# Bypass_FPGA_1V2.net
KiCad netlist of a schematic drawn in Altium Designer
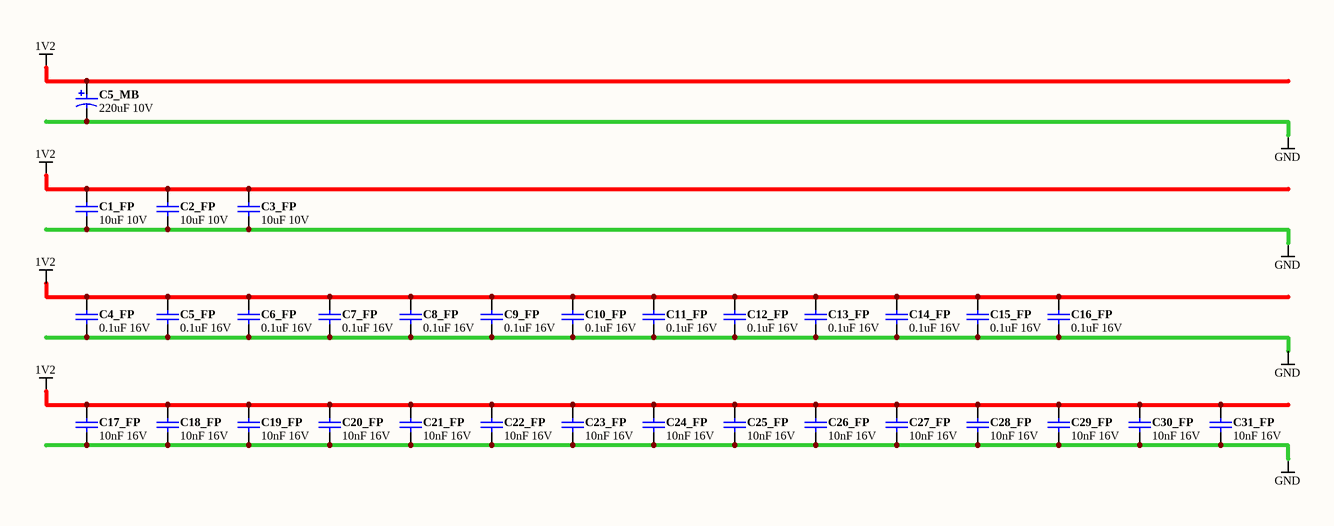
[diagram p0: Bypass_FPGA_1V2.SCHDOC]

(export (version "E")
  (design (tool "Eeschema 10.0.6"))
  (components
    (comp (ref "C1_FP")
      (value "10uF 10V")
      (footprint "CAPC2012-STAR")
      (description "Capacitor, Ceramic, 10uF 10% 10V 0805 (2012) X5R")
      (fields (field (name "TOLERANCE") "10 %"))
      (libsource (lib "AltiumDesignLibrary") (part "CAP-NP"))
    )
    (comp (ref "C2_FP")
      (value "10uF 10V")
      (footprint "CAPC2012-STAR")
      (description "Capacitor, Ceramic, 10uF 10% 10V 0805 (2012) X5R")
      (fields (field (name "TOLERANCE") "10 %"))
      (libsource (lib "AltiumDesignLibrary") (part "CAP-NP"))
    )
    (comp (ref "C3_FP")
      (value "10uF 10V")
      (footprint "CAPC2012-STAR")
      (description "Capacitor, Ceramic, 10uF 10% 10V 0805 (2012) X5R")
      (fields (field (name "TOLERANCE") "10 %"))
      (libsource (lib "AltiumDesignLibrary") (part "CAP-NP"))
    )
    (comp (ref "C4_FP")
      (value "0.1uF 16V")
      (footprint "CAPC1005-STAR")
      (description "Capacitor, Ceramic, 0.1uF 10% 16V 0402 (1005) X7R")
      (fields (field (name "TOLERANCE") "10 %"))
      (libsource (lib "AltiumDesignLibrary") (part "CAP-NP"))
    )
    (comp (ref "C5_FP")
      (value "0.1uF 16V")
      (footprint "CAPC1005-STAR")
      (description "Capacitor, Ceramic, 0.1uF 10% 16V 0402 (1005) X7R")
      (fields (field (name "TOLERANCE") "10 %"))
      (libsource (lib "AltiumDesignLibrary") (part "CAP-NP"))
    )
    (comp (ref "C5_MB")
      (value "220uF 10V")
      (footprint "CAPC7343-STAR")
      (description "Capacitor, Tantalum, 220uF 10% 10V MCCT-D (7343-31)")
      (fields (field (name "TOLERANCE") "10 %"))
      (libsource (lib "AltiumDesignLibrary") (part "CAP-P"))
    )
    (comp (ref "C6_FP")
      (value "0.1uF 16V")
      (footprint "CAPC1005-STAR")
      (description "Capacitor, Ceramic, 0.1uF 10% 16V 0402 (1005) X7R")
      (fields (field (name "TOLERANCE") "10 %"))
      (libsource (lib "AltiumDesignLibrary") (part "CAP-NP"))
    )
    (comp (ref "C7_FP")
      (value "0.1uF 16V")
      (footprint "CAPC1005-STAR")
      (description "Capacitor, Ceramic, 0.1uF 10% 16V 0402 (1005) X7R")
      (fields (field (name "TOLERANCE") "10 %"))
      (libsource (lib "AltiumDesignLibrary") (part "CAP-NP"))
    )
    (comp (ref "C8_FP")
      (value "0.1uF 16V")
      (footprint "CAPC1005-STAR")
      (description "Capacitor, Ceramic, 0.1uF 10% 16V 0402 (1005) X7R")
      (fields (field (name "TOLERANCE") "10 %"))
      (libsource (lib "AltiumDesignLibrary") (part "CAP-NP"))
    )
    (comp (ref "C9_FP")
      (value "0.1uF 16V")
      (footprint "CAPC1005-STAR")
      (description "Capacitor, Ceramic, 0.1uF 10% 16V 0402 (1005) X7R")
      (fields (field (name "TOLERANCE") "10 %"))
      (libsource (lib "AltiumDesignLibrary") (part "CAP-NP"))
    )
    (comp (ref "C10_FP")
      (value "0.1uF 16V")
      (footprint "CAPC1005-STAR")
      (description "Capacitor, Ceramic, 0.1uF 10% 16V 0402 (1005) X7R")
      (fields (field (name "TOLERANCE") "10 %"))
      (libsource (lib "AltiumDesignLibrary") (part "CAP-NP"))
    )
    (comp (ref "C11_FP")
      (value "0.1uF 16V")
      (footprint "CAPC1005-STAR")
      (description "Capacitor, Ceramic, 0.1uF 10% 16V 0402 (1005) X7R")
      (fields (field (name "TOLERANCE") "10 %"))
      (libsource (lib "AltiumDesignLibrary") (part "CAP-NP"))
    )
    (comp (ref "C12_FP")
      (value "0.1uF 16V")
      (footprint "CAPC1005-STAR")
      (description "Capacitor, Ceramic, 0.1uF 10% 16V 0402 (1005) X7R")
      (fields (field (name "TOLERANCE") "10 %"))
      (libsource (lib "AltiumDesignLibrary") (part "CAP-NP"))
    )
    (comp (ref "C13_FP")
      (value "0.1uF 16V")
      (footprint "CAPC1005-STAR")
      (description "Capacitor, Ceramic, 0.1uF 10% 16V 0402 (1005) X7R")
      (fields (field (name "TOLERANCE") "10 %"))
      (libsource (lib "AltiumDesignLibrary") (part "CAP-NP"))
    )
    (comp (ref "C14_FP")
      (value "0.1uF 16V")
      (footprint "CAPC1005-STAR")
      (description "Capacitor, Ceramic, 0.1uF 10% 16V 0402 (1005) X7R")
      (fields (field (name "TOLERANCE") "10 %"))
      (libsource (lib "AltiumDesignLibrary") (part "CAP-NP"))
    )
    (comp (ref "C15_FP")
      (value "0.1uF 16V")
      (footprint "CAPC1005-STAR")
      (description "Capacitor, Ceramic, 0.1uF 10% 16V 0402 (1005) X7R")
      (fields (field (name "TOLERANCE") "10 %"))
      (libsource (lib "AltiumDesignLibrary") (part "CAP-NP"))
    )
    (comp (ref "C16_FP")
      (value "0.1uF 16V")
      (footprint "CAPC1005-STAR")
      (description "Capacitor, Ceramic, 0.1uF 10% 16V 0402 (1005) X7R")
      (fields (field (name "TOLERANCE") "10 %"))
      (libsource (lib "AltiumDesignLibrary") (part "CAP-NP"))
    )
    (comp (ref "C17_FP")
      (value "10nF 16V")
      (footprint "CAPC1005-STAR")
      (description "Capacitor, Ceramic, 10nF 10% 16V 0402 (1005) X7R")
      (fields (field (name "TOLERANCE") "10 %"))
      (libsource (lib "AltiumDesignLibrary") (part "CAP-NP"))
    )
    (comp (ref "C18_FP")
      (value "10nF 16V")
      (footprint "CAPC1005-STAR")
      (description "Capacitor, Ceramic, 10nF 10% 16V 0402 (1005) X7R")
      (fields (field (name "TOLERANCE") "10 %"))
      (libsource (lib "AltiumDesignLibrary") (part "CAP-NP"))
    )
    (comp (ref "C19_FP")
      (value "10nF 16V")
      (footprint "CAPC1005-STAR")
      (description "Capacitor, Ceramic, 10nF 10% 16V 0402 (1005) X7R")
      (fields (field (name "TOLERANCE") "10 %"))
      (libsource (lib "AltiumDesignLibrary") (part "CAP-NP"))
    )
    (comp (ref "C20_FP")
      (value "10nF 16V")
      (footprint "CAPC1005-STAR")
      (description "Capacitor, Ceramic, 10nF 10% 16V 0402 (1005) X7R")
      (fields (field (name "TOLERANCE") "10 %"))
      (libsource (lib "AltiumDesignLibrary") (part "CAP-NP"))
    )
    (comp (ref "C21_FP")
      (value "10nF 16V")
      (footprint "CAPC1005-STAR")
      (description "Capacitor, Ceramic, 10nF 10% 16V 0402 (1005) X7R")
      (fields (field (name "TOLERANCE") "10 %"))
      (libsource (lib "AltiumDesignLibrary") (part "CAP-NP"))
    )
    (comp (ref "C22_FP")
      (value "10nF 16V")
      (footprint "CAPC1005-STAR")
      (description "Capacitor, Ceramic, 10nF 10% 16V 0402 (1005) X7R")
      (fields (field (name "TOLERANCE") "10 %"))
      (libsource (lib "AltiumDesignLibrary") (part "CAP-NP"))
    )
    (comp (ref "C23_FP")
      (value "10nF 16V")
      (footprint "CAPC1005-STAR")
      (description "Capacitor, Ceramic, 10nF 10% 16V 0402 (1005) X7R")
      (fields (field (name "TOLERANCE") "10 %"))
      (libsource (lib "AltiumDesignLibrary") (part "CAP-NP"))
    )
    (comp (ref "C24_FP")
      (value "10nF 16V")
      (footprint "CAPC1005-STAR")
      (description "Capacitor, Ceramic, 10nF 10% 16V 0402 (1005) X7R")
      (fields (field (name "TOLERANCE") "10 %"))
      (libsource (lib "AltiumDesignLibrary") (part "CAP-NP"))
    )
    (comp (ref "C25_FP")
      (value "10nF 16V")
      (footprint "CAPC1005-STAR")
      (description "Capacitor, Ceramic, 10nF 10% 16V 0402 (1005) X7R")
      (fields (field (name "TOLERANCE") "10 %"))
      (libsource (lib "AltiumDesignLibrary") (part "CAP-NP"))
    )
    (comp (ref "C26_FP")
      (value "10nF 16V")
      (footprint "CAPC1005-STAR")
      (description "Capacitor, Ceramic, 10nF 10% 16V 0402 (1005) X7R")
      (fields (field (name "TOLERANCE") "10 %"))
      (libsource (lib "AltiumDesignLibrary") (part "CAP-NP"))
    )
    (comp (ref "C27_FP")
      (value "10nF 16V")
      (footprint "CAPC1005-STAR")
      (description "Capacitor, Ceramic, 10nF 10% 16V 0402 (1005) X7R")
      (fields (field (name "TOLERANCE") "10 %"))
      (libsource (lib "AltiumDesignLibrary") (part "CAP-NP"))
    )
    (comp (ref "C28_FP")
      (value "10nF 16V")
      (footprint "CAPC1005-STAR")
      (description "Capacitor, Ceramic, 10nF 10% 16V 0402 (1005) X7R")
      (fields (field (name "TOLERANCE") "10 %"))
      (libsource (lib "AltiumDesignLibrary") (part "CAP-NP"))
    )
    (comp (ref "C29_FP")
      (value "10nF 16V")
      (footprint "CAPC1005-STAR")
      (description "Capacitor, Ceramic, 10nF 10% 16V 0402 (1005) X7R")
      (fields (field (name "TOLERANCE") "10 %"))
      (libsource (lib "AltiumDesignLibrary") (part "CAP-NP"))
    )
    (comp (ref "C30_FP")
      (value "10nF 16V")
      (footprint "CAPC1005-STAR")
      (description "Capacitor, Ceramic, 10nF 10% 16V 0402 (1005) X7R")
      (fields (field (name "TOLERANCE") "10 %"))
      (libsource (lib "AltiumDesignLibrary") (part "CAP-NP"))
    )
    (comp (ref "C31_FP")
      (value "10nF 16V")
      (footprint "CAPC1005-STAR")
      (description "Capacitor, Ceramic, 10nF 10% 16V 0402 (1005) X7R")
      (fields (field (name "TOLERANCE") "10 %"))
      (libsource (lib "AltiumDesignLibrary") (part "CAP-NP"))
    )
  )
  (nets
    (net (code "1") (name "1V2") (class "Default")
      (node (ref "C10_FP") (pin "1") (pinfunction "1_1") (pintype "passive"))
      (node (ref "C11_FP") (pin "1") (pinfunction "1_1") (pintype "passive"))
      (node (ref "C12_FP") (pin "1") (pinfunction "1_1") (pintype "passive"))
      (node (ref "C13_FP") (pin "1") (pinfunction "1_1") (pintype "passive"))
      (node (ref "C14_FP") (pin "1") (pinfunction "1_1") (pintype "passive"))
      (node (ref "C15_FP") (pin "1") (pinfunction "1_1") (pintype "passive"))
      (node (ref "C16_FP") (pin "1") (pinfunction "1_1") (pintype "passive"))
      (node (ref "C17_FP") (pin "1") (pinfunction "1_1") (pintype "passive"))
      (node (ref "C18_FP") (pin "1") (pinfunction "1_1") (pintype "passive"))
      (node (ref "C19_FP") (pin "1") (pinfunction "1_1") (pintype "passive"))
      (node (ref "C1_FP") (pin "1") (pinfunction "1_1") (pintype "passive"))
      (node (ref "C20_FP") (pin "1") (pinfunction "1_1") (pintype "passive"))
      (node (ref "C21_FP") (pin "1") (pinfunction "1_1") (pintype "passive"))
      (node (ref "C22_FP") (pin "1") (pinfunction "1_1") (pintype "passive"))
      (node (ref "C23_FP") (pin "1") (pinfunction "1_1") (pintype "passive"))
      (node (ref "C24_FP") (pin "1") (pinfunction "1_1") (pintype "passive"))
      (node (ref "C25_FP") (pin "1") (pinfunction "1_1") (pintype "passive"))
      (node (ref "C26_FP") (pin "1") (pinfunction "1_1") (pintype "passive"))
      (node (ref "C27_FP") (pin "1") (pinfunction "1_1") (pintype "passive"))
      (node (ref "C28_FP") (pin "1") (pinfunction "1_1") (pintype "passive"))
      (node (ref "C29_FP") (pin "1") (pinfunction "1_1") (pintype "passive"))
      (node (ref "C2_FP") (pin "1") (pinfunction "1_1") (pintype "passive"))
      (node (ref "C30_FP") (pin "1") (pinfunction "1_1") (pintype "passive"))
      (node (ref "C31_FP") (pin "1") (pinfunction "1_1") (pintype "passive"))
      (node (ref "C3_FP") (pin "1") (pinfunction "1_1") (pintype "passive"))
      (node (ref "C4_FP") (pin "1") (pinfunction "1_1") (pintype "passive"))
      (node (ref "C5_FP") (pin "1") (pinfunction "1_1") (pintype "passive"))
      (node (ref "C5_MB") (pin "1") (pinfunction "1_1") (pintype "passive"))
      (node (ref "C6_FP") (pin "1") (pinfunction "1_1") (pintype "passive"))
      (node (ref "C7_FP") (pin "1") (pinfunction "1_1") (pintype "passive"))
      (node (ref "C8_FP") (pin "1") (pinfunction "1_1") (pintype "passive"))
      (node (ref "C9_FP") (pin "1") (pinfunction "1_1") (pintype "passive"))
    )
    (net (code "2") (name "GND") (class "Default")
      (node (ref "C10_FP") (pin "2") (pinfunction "2_2") (pintype "passive"))
      (node (ref "C11_FP") (pin "2") (pinfunction "2_2") (pintype "passive"))
      (node (ref "C12_FP") (pin "2") (pinfunction "2_2") (pintype "passive"))
      (node (ref "C13_FP") (pin "2") (pinfunction "2_2") (pintype "passive"))
      (node (ref "C14_FP") (pin "2") (pinfunction "2_2") (pintype "passive"))
      (node (ref "C15_FP") (pin "2") (pinfunction "2_2") (pintype "passive"))
      (node (ref "C16_FP") (pin "2") (pinfunction "2_2") (pintype "passive"))
      (node (ref "C17_FP") (pin "2") (pinfunction "2_2") (pintype "passive"))
      (node (ref "C18_FP") (pin "2") (pinfunction "2_2") (pintype "passive"))
      (node (ref "C19_FP") (pin "2") (pinfunction "2_2") (pintype "passive"))
      (node (ref "C1_FP") (pin "2") (pinfunction "2_2") (pintype "passive"))
      (node (ref "C20_FP") (pin "2") (pinfunction "2_2") (pintype "passive"))
      (node (ref "C21_FP") (pin "2") (pinfunction "2_2") (pintype "passive"))
      (node (ref "C22_FP") (pin "2") (pinfunction "2_2") (pintype "passive"))
      (node (ref "C23_FP") (pin "2") (pinfunction "2_2") (pintype "passive"))
      (node (ref "C24_FP") (pin "2") (pinfunction "2_2") (pintype "passive"))
      (node (ref "C25_FP") (pin "2") (pinfunction "2_2") (pintype "passive"))
      (node (ref "C26_FP") (pin "2") (pinfunction "2_2") (pintype "passive"))
      (node (ref "C27_FP") (pin "2") (pinfunction "2_2") (pintype "passive"))
      (node (ref "C28_FP") (pin "2") (pinfunction "2_2") (pintype "passive"))
      (node (ref "C29_FP") (pin "2") (pinfunction "2_2") (pintype "passive"))
      (node (ref "C2_FP") (pin "2") (pinfunction "2_2") (pintype "passive"))
      (node (ref "C30_FP") (pin "2") (pinfunction "2_2") (pintype "passive"))
      (node (ref "C31_FP") (pin "2") (pinfunction "2_2") (pintype "passive"))
      (node (ref "C3_FP") (pin "2") (pinfunction "2_2") (pintype "passive"))
      (node (ref "C4_FP") (pin "2") (pinfunction "2_2") (pintype "passive"))
      (node (ref "C5_FP") (pin "2") (pinfunction "2_2") (pintype "passive"))
      (node (ref "C5_MB") (pin "2") (pinfunction "2_2") (pintype "passive"))
      (node (ref "C6_FP") (pin "2") (pinfunction "2_2") (pintype "passive"))
      (node (ref "C7_FP") (pin "2") (pinfunction "2_2") (pintype "passive"))
      (node (ref "C8_FP") (pin "2") (pinfunction "2_2") (pintype "passive"))
      (node (ref "C9_FP") (pin "2") (pinfunction "2_2") (pintype "passive"))
    )
  )
)
